# Three_Phase_Rectifier_Regulator.net
KiCad netlist of a schematic drawn in Altium Designer
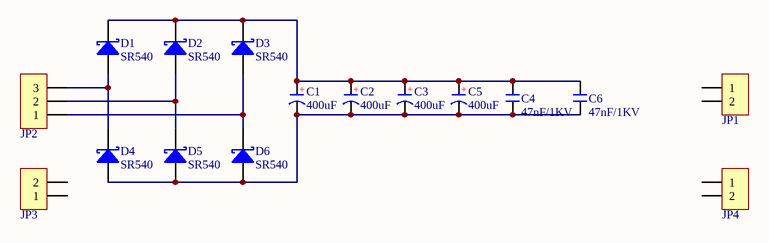
[diagram p0: Three_Phase_Rectifier_Regulator.SchDoc]

(export (version "E")
  (design (tool "Eeschema 10.0.6"))
  (components
    (comp (ref "C1")
      (value "400uF")
      (footprint "CAP 7.5*16*25 - GD")
      (description "直插电解电容")
      (libsource (lib "01 - 电容-电阻-电感") (part "CE"))
    )
    (comp (ref "C2")
      (value "400uF")
      (footprint "CAP 7.5*16*25 - GD")
      (description "直插电解电容")
      (libsource (lib "01 - 电容-电阻-电感") (part "CE"))
    )
    (comp (ref "C3")
      (value "400uF")
      (footprint "CAP 7.5*16*25 - GD")
      (description "直插电解电容")
      (libsource (lib "01 - 电容-电阻-电感") (part "CE"))
    )
    (comp (ref "C4")
      (value "47nF/1KV")
      (footprint "CY 7.5*12*5")
      (description "安规Y电容")
      (libsource (lib "01 - 电容-电阻-电感") (part "CY"))
    )
    (comp (ref "C5")
      (value "400uF")
      (footprint "CAP 7.5*16*25 - GD")
      (description "直插电解电容")
      (libsource (lib "01 - 电容-电阻-电感") (part "CE"))
    )
    (comp (ref "C6")
      (value "47nF/1KV")
      (footprint "CY 7.5*12*5")
      (description "安规Y电容")
      (libsource (lib "01 - 电容-电阻-电感") (part "CY"))
    )
    (comp (ref "D1")
      (value "SR540")
      (footprint "DO-27")
      (description "肖特基二极管")
      (libsource (lib "02 - 二极管(LED)-三极管-整流桥") (part "SR540"))
    )
    (comp (ref "D2")
      (value "SR540")
      (footprint "DO-27")
      (description "肖特基二极管")
      (libsource (lib "02 - 二极管(LED)-三极管-整流桥") (part "SR540"))
    )
    (comp (ref "D3")
      (value "SR540")
      (footprint "DO-27")
      (description "肖特基二极管")
      (libsource (lib "02 - 二极管(LED)-三极管-整流桥") (part "SR540"))
    )
    (comp (ref "D4")
      (value "SR540")
      (footprint "DO-27")
      (description "肖特基二极管")
      (libsource (lib "02 - 二极管(LED)-三极管-整流桥") (part "SR540"))
    )
    (comp (ref "D5")
      (value "SR540")
      (footprint "DO-27")
      (description "肖特基二极管")
      (libsource (lib "02 - 二极管(LED)-三极管-整流桥") (part "SR540"))
    )
    (comp (ref "D6")
      (value "SR540")
      (footprint "DO-27")
      (description "肖特基二极管")
      (libsource (lib "02 - 二极管(LED)-三极管-整流桥") (part "SR540"))
    )
    (comp (ref "JP1")
      (value "HDR-1X2")
      (footprint "KF7620-2P")
      (description "2P接插件")
      (libsource (lib "24 - 接插件-脚距7.62mm (300mil) ") (part "Header 2"))
    )
    (comp (ref "JP2")
      (value "HDR-1X3")
      (footprint "KF7620-3P")
      (description "3P接插件")
      (libsource (lib "24 - 接插件-脚距7.62mm (300mil) ") (part "Header 3"))
    )
    (comp (ref "JP3")
      (value "HDR-1X2")
      (footprint "KF7620-2P")
      (description "2P接插件")
      (libsource (lib "") (part "Header 2_1"))
    )
    (comp (ref "JP4")
      (value "HDR-1X2")
      (footprint "KF7620-2P")
      (description "2P接插件")
      (libsource (lib "24 - 接插件-脚距7.62mm (300mil) ") (part "Header 2"))
    )
  )
  (nets
    (net (code "1") (name "Net-(C1-A)") (class "Default")
      (node (ref "C1") (pin "1") (pinfunction "A_1") (pintype "passive"))
      (node (ref "C2") (pin "1") (pinfunction "A_1") (pintype "passive"))
      (node (ref "C3") (pin "1") (pinfunction "A_1") (pintype "passive"))
      (node (ref "C4") (pin "2") (pinfunction "2_2") (pintype "passive"))
      (node (ref "C5") (pin "1") (pinfunction "A_1") (pintype "passive"))
      (node (ref "C6") (pin "2") (pinfunction "2_2") (pintype "passive"))
      (node (ref "D1") (pin "2") (pinfunction "K_2") (pintype "passive"))
      (node (ref "D2") (pin "2") (pinfunction "K_2") (pintype "passive"))
      (node (ref "D3") (pin "2") (pinfunction "K_2") (pintype "passive"))
    )
    (net (code "2") (name "Net-(C1-K)") (class "Default")
      (node (ref "C1") (pin "2") (pinfunction "K_2") (pintype "passive"))
      (node (ref "C2") (pin "2") (pinfunction "K_2") (pintype "passive"))
      (node (ref "C3") (pin "2") (pinfunction "K_2") (pintype "passive"))
      (node (ref "C4") (pin "1") (pinfunction "1_1") (pintype "passive"))
      (node (ref "C5") (pin "2") (pinfunction "K_2") (pintype "passive"))
      (node (ref "C6") (pin "1") (pinfunction "1_1") (pintype "passive"))
      (node (ref "D4") (pin "1") (pinfunction "A_1") (pintype "passive"))
      (node (ref "D5") (pin "1") (pinfunction "A_1") (pintype "passive"))
      (node (ref "D6") (pin "1") (pinfunction "A_1") (pintype "passive"))
    )
    (net (code "3") (name "Net-(D1-A)") (class "Default")
      (node (ref "D1") (pin "1") (pinfunction "A_1") (pintype "passive"))
      (node (ref "D4") (pin "2") (pinfunction "K_2") (pintype "passive"))
      (node (ref "JP2") (pin "3") (pinfunction "3_3") (pintype "passive"))
    )
    (net (code "4") (name "Net-(D2-A)") (class "Default")
      (node (ref "D2") (pin "1") (pinfunction "A_1") (pintype "passive"))
      (node (ref "D5") (pin "2") (pinfunction "K_2") (pintype "passive"))
      (node (ref "JP2") (pin "2") (pinfunction "2_2") (pintype "passive"))
    )
    (net (code "5") (name "Net-(D3-A)") (class "Default")
      (node (ref "D3") (pin "1") (pinfunction "A_1") (pintype "passive"))
      (node (ref "D6") (pin "2") (pinfunction "K_2") (pintype "passive"))
      (node (ref "JP2") (pin "1") (pinfunction "1_1") (pintype "passive"))
    )
    (net (code "6") (name "unconnected-(JP1-Pad1)") (class "Default")
      (node (ref "JP1") (pin "1") (pinfunction "1_1") (pintype "passive"))
    )
    (net (code "7") (name "unconnected-(JP1-Pad2)") (class "Default")
      (node (ref "JP1") (pin "2") (pinfunction "2_2") (pintype "passive"))
    )
    (net (code "8") (name "unconnected-(JP3-Pad1)") (class "Default")
      (node (ref "JP3") (pin "1") (pinfunction "1_1") (pintype "passive"))
    )
    (net (code "9") (name "unconnected-(JP3-Pad2)") (class "Default")
      (node (ref "JP3") (pin "2") (pinfunction "2_2") (pintype "passive"))
    )
    (net (code "10") (name "unconnected-(JP4-Pad1)") (class "Default")
      (node (ref "JP4") (pin "1") (pinfunction "1_1") (pintype "passive"))
    )
    (net (code "11") (name "unconnected-(JP4-Pad2)") (class "Default")
      (node (ref "JP4") (pin "2") (pinfunction "2_2") (pintype "passive"))
    )
  )
)
